# CapMeter-LCD-16F628A.net
KiCad netlist of a schematic drawn in EAGLE
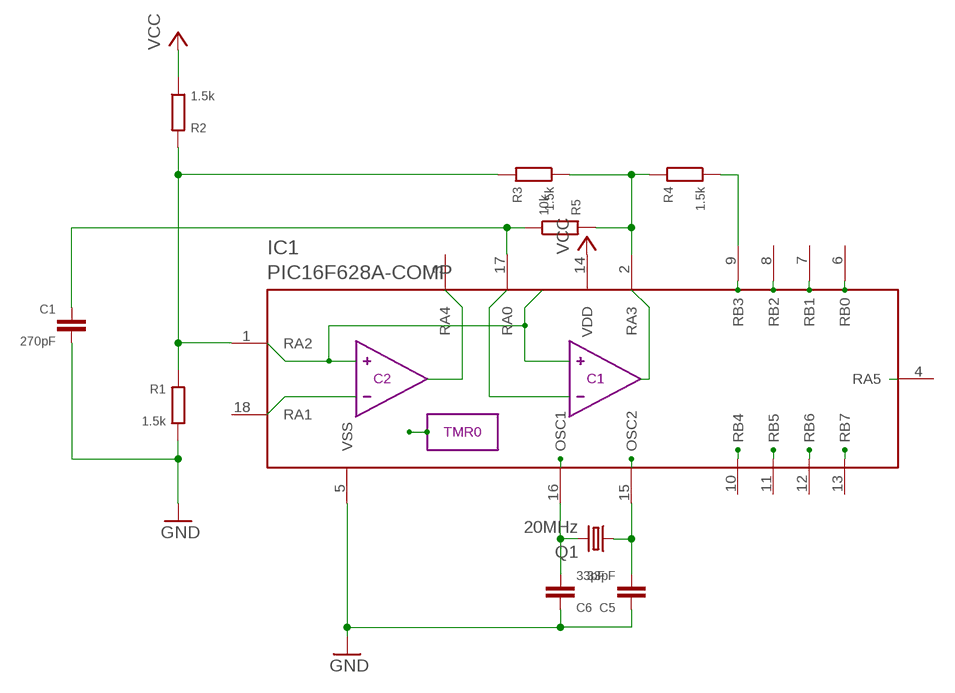
[diagram p0: schematic, sheet 1]

(export (version "E")
  (design (tool "Eeschema 10.0.6"))
  (components
    (comp (ref "C1")
      (value "270pF")
      (footprint "eagle-import:C050-020X036")
      (libsource (lib "eagle-import") (part "C050-020X036"))
    )
    (comp (ref "C5")
      (value "33pF")
      (footprint "eagle-import:C025-020X036")
      (libsource (lib "eagle-import") (part "C025-020X036"))
    )
    (comp (ref "C6")
      (value "33pF")
      (footprint "eagle-import:C025-020X036")
      (libsource (lib "eagle-import") (part "C025-020X036"))
    )
    (comp (ref "IC1")
      (value "PIC16F628A-COMP")
      (footprint "eagle-import:DIL18-3_V")
      (libsource (lib "eagle-import") (part "PIC16F628A-COMP"))
    )
    (comp (ref "Q1")
      (value "20MHz")
      (footprint "eagle-import:HC49")
      (libsource (lib "eagle-import") (part "CRYSTALHC49"))
    )
    (comp (ref "R1")
      (value "1.5k")
      (footprint "eagle-import:0204_10")
      (libsource (lib "eagle-import") (part "R0204/10"))
    )
    (comp (ref "R2")
      (value "1.5k")
      (footprint "eagle-import:0204_10")
      (libsource (lib "eagle-import") (part "R0204/10"))
    )
    (comp (ref "R3")
      (value "1.5k")
      (footprint "eagle-import:0204_10")
      (libsource (lib "eagle-import") (part "R0204/10"))
    )
    (comp (ref "R4")
      (value "1.5k")
      (footprint "eagle-import:0204_10")
      (libsource (lib "eagle-import") (part "R0204/10"))
    )
    (comp (ref "R5")
      (value "10k")
      (footprint "eagle-import:0204_10")
      (libsource (lib "eagle-import") (part "R0204/10"))
    )
  )
  (nets
    (net (code "1") (name "GND") (class "Default")
      (node (ref "C1") (pin "2") (pinfunction "2_2") (pintype "passive"))
      (node (ref "C5") (pin "1") (pinfunction "1_1") (pintype "passive"))
      (node (ref "C6") (pin "1") (pinfunction "1_1") (pintype "passive"))
      (node (ref "IC1") (pin "5") (pinfunction "VSS_5") (pintype "passive"))
      (node (ref "R1") (pin "1") (pinfunction "1_1") (pintype "passive"))
    )
    (net (code "2") (name "Net-(IC1-OSC1)") (class "Default")
      (node (ref "C6") (pin "2") (pinfunction "2_2") (pintype "passive"))
      (node (ref "IC1") (pin "16") (pinfunction "OSC1_16") (pintype "passive"))
      (node (ref "Q1") (pin "2") (pinfunction "2_2") (pintype "passive"))
    )
    (net (code "3") (name "Net-(IC1-OSC2)") (class "Default")
      (node (ref "C5") (pin "2") (pinfunction "2_2") (pintype "passive"))
      (node (ref "IC1") (pin "15") (pinfunction "OSC2_15") (pintype "passive"))
      (node (ref "Q1") (pin "1") (pinfunction "1_1") (pintype "passive"))
    )
    (net (code "4") (name "Net-(IC1-RA0)") (class "Default")
      (node (ref "C1") (pin "1") (pinfunction "1_1") (pintype "passive"))
      (node (ref "IC1") (pin "17") (pinfunction "RA0_17") (pintype "passive"))
      (node (ref "R5") (pin "1") (pinfunction "1_1") (pintype "passive"))
    )
    (net (code "5") (name "Net-(IC1-RA2)") (class "Default")
      (node (ref "IC1") (pin "1") (pinfunction "RA2_1") (pintype "passive"))
      (node (ref "R1") (pin "2") (pinfunction "2_2") (pintype "passive"))
      (node (ref "R2") (pin "2") (pinfunction "2_2") (pintype "passive"))
      (node (ref "R3") (pin "2") (pinfunction "2_2") (pintype "passive"))
    )
    (net (code "6") (name "Net-(IC1-RA3)") (class "Default")
      (node (ref "IC1") (pin "2") (pinfunction "RA3_2") (pintype "passive"))
      (node (ref "R3") (pin "1") (pinfunction "1_1") (pintype "passive"))
      (node (ref "R4") (pin "2") (pinfunction "2_2") (pintype "passive"))
      (node (ref "R5") (pin "2") (pinfunction "2_2") (pintype "passive"))
    )
    (net (code "7") (name "Net-(IC1-RB3)") (class "Default")
      (node (ref "IC1") (pin "9") (pinfunction "RB3_9") (pintype "passive"))
      (node (ref "R4") (pin "1") (pinfunction "1_1") (pintype "passive"))
    )
    (net (code "8") (name "VCC") (class "Default")
      (node (ref "IC1") (pin "14") (pinfunction "VDD_14") (pintype "passive"))
      (node (ref "R2") (pin "1") (pinfunction "1_1") (pintype "passive"))
    )
    (net (code "9") (name "unconnected-(IC1-RA1-Pad18)") (class "Default")
      (node (ref "IC1") (pin "18") (pinfunction "RA1_18") (pintype "passive"))
    )
    (net (code "10") (name "unconnected-(IC1-RA4-Pad3)") (class "Default")
      (node (ref "IC1") (pin "3") (pinfunction "RA4_3") (pintype "passive"))
    )
    (net (code "11") (name "unconnected-(IC1-RA5-Pad4)") (class "Default")
      (node (ref "IC1") (pin "4") (pinfunction "RA5_4") (pintype "passive"))
    )
    (net (code "12") (name "unconnected-(IC1-RB0-Pad6)") (class "Default")
      (node (ref "IC1") (pin "6") (pinfunction "RB0_6") (pintype "passive"))
    )
    (net (code "13") (name "unconnected-(IC1-RB1-Pad7)") (class "Default")
      (node (ref "IC1") (pin "7") (pinfunction "RB1_7") (pintype "passive"))
    )
    (net (code "14") (name "unconnected-(IC1-RB2-Pad8)") (class "Default")
      (node (ref "IC1") (pin "8") (pinfunction "RB2_8") (pintype "passive"))
    )
    (net (code "15") (name "unconnected-(IC1-RB4-Pad10)") (class "Default")
      (node (ref "IC1") (pin "10") (pinfunction "RB4_10") (pintype "passive"))
    )
    (net (code "16") (name "unconnected-(IC1-RB5-Pad11)") (class "Default")
      (node (ref "IC1") (pin "11") (pinfunction "RB5_11") (pintype "passive"))
    )
    (net (code "17") (name "unconnected-(IC1-RB6-Pad12)") (class "Default")
      (node (ref "IC1") (pin "12") (pinfunction "RB6_12") (pintype "passive"))
    )
    (net (code "18") (name "unconnected-(IC1-RB7-Pad13)") (class "Default")
      (node (ref "IC1") (pin "13") (pinfunction "RB7_13") (pintype "passive"))
    )
  )
)
